# SLED.net
KiCad netlist of a schematic drawn in Altium Designer
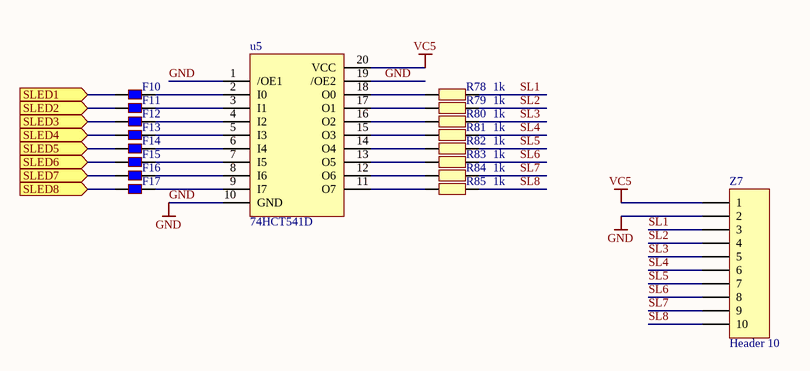
[diagram p0: SLED.SchDoc]

(export (version "E")
  (design (tool "Eeschema 10.0.6"))
  (components
    (comp (ref "F10")
      (value "BLM18BB141SN1D")
      (footprint "0805L")
      (description "Koralik ferrytowy")
      (libsource (lib "*") (part "1812"))
    )
    (comp (ref "F11")
      (value "BLM18BB141SN1D")
      (footprint "0805L")
      (description "Koralik ferrytowy")
      (libsource (lib "*") (part "1812"))
    )
    (comp (ref "F12")
      (value "BLM18BB141SN1D")
      (footprint "0805L")
      (description "Koralik ferrytowy")
      (libsource (lib "*") (part "1812"))
    )
    (comp (ref "F13")
      (value "BLM18BB141SN1D")
      (footprint "0805L")
      (description "Koralik ferrytowy")
      (libsource (lib "*") (part "1812"))
    )
    (comp (ref "F14")
      (value "BLM18BB141SN1D")
      (footprint "0805L")
      (description "Koralik ferrytowy")
      (libsource (lib "*") (part "1812"))
    )
    (comp (ref "F15")
      (value "BLM18BB141SN1D")
      (footprint "0805L")
      (description "Koralik ferrytowy")
      (libsource (lib "*") (part "1812"))
    )
    (comp (ref "F16")
      (value "BLM18BB141SN1D")
      (footprint "0805L")
      (description "Koralik ferrytowy")
      (libsource (lib "*") (part "1812"))
    )
    (comp (ref "F17")
      (value "BLM18BB141SN1D")
      (footprint "0805L")
      (description "Koralik ferrytowy")
      (libsource (lib "*") (part "1812"))
    )
    (comp (ref "R78") (value "1k") (footprint "0805R") (libsource (lib "*") (part "RES3")))
    (comp (ref "R79") (value "1k") (footprint "0805R") (libsource (lib "*") (part "RES3")))
    (comp (ref "R80") (value "1k") (footprint "0805R") (libsource (lib "*") (part "RES3")))
    (comp (ref "R81") (value "1k") (footprint "0805R") (libsource (lib "*") (part "RES3")))
    (comp (ref "R82") (value "1k") (footprint "0805R") (libsource (lib "*") (part "RES3")))
    (comp (ref "R83") (value "1k") (footprint "0805R") (libsource (lib "*") (part "RES3")))
    (comp (ref "R84") (value "1k") (footprint "0805R") (libsource (lib "*") (part "RES3")))
    (comp (ref "R85") (value "1k") (footprint "0805R") (libsource (lib "*") (part "RES3")))
    (comp (ref "u5") (value "74HCT541D") (footprint "SMD20") (libsource (lib "ElhosSchLib") (part "74541")))
    (comp (ref "Z7")
      (value "Header 10")
      (footprint "ARC-L-10-3.5")
      (description "Header, 10-Pin")
      (fields (field (name "PUBLISHER") "Altium Limited"))
      (libsource (lib "Miscellaneous Connectors") (part "Header 10"))
    )
  )
  (nets
    (net (code "1") (name "/SL1") (class "Default")
      (node (ref "R78") (pin "2") (pintype "passive"))
      (node (ref "Z7") (pin "3") (pinfunction "3_3") (pintype "passive"))
    )
    (net (code "2") (name "/SL2") (class "Default")
      (node (ref "R79") (pin "2") (pintype "passive"))
      (node (ref "Z7") (pin "4") (pinfunction "4_4") (pintype "passive"))
    )
    (net (code "3") (name "/SL3") (class "Default")
      (node (ref "R80") (pin "2") (pintype "passive"))
      (node (ref "Z7") (pin "5") (pinfunction "5_5") (pintype "passive"))
    )
    (net (code "4") (name "/SL4") (class "Default")
      (node (ref "R81") (pin "2") (pintype "passive"))
      (node (ref "Z7") (pin "6") (pinfunction "6_6") (pintype "passive"))
    )
    (net (code "5") (name "/SL5") (class "Default")
      (node (ref "R82") (pin "2") (pintype "passive"))
      (node (ref "Z7") (pin "7") (pinfunction "7_7") (pintype "passive"))
    )
    (net (code "6") (name "/SL6") (class "Default")
      (node (ref "R83") (pin "2") (pintype "passive"))
      (node (ref "Z7") (pin "8") (pinfunction "8_8") (pintype "passive"))
    )
    (net (code "7") (name "/SL7") (class "Default")
      (node (ref "R84") (pin "2") (pintype "passive"))
      (node (ref "Z7") (pin "9") (pinfunction "9_9") (pintype "passive"))
    )
    (net (code "8") (name "/SL8") (class "Default")
      (node (ref "R85") (pin "2") (pintype "passive"))
      (node (ref "Z7") (pin "10") (pinfunction "10_10") (pintype "passive"))
    )
    (net (code "9") (name "/SLED1") (class "Default") (node (ref "F10") (pin "2") (pintype "passive")))
    (net (code "10") (name "/SLED2") (class "Default") (node (ref "F11") (pin "2") (pintype "passive")))
    (net (code "11") (name "/SLED3") (class "Default") (node (ref "F12") (pin "2") (pintype "passive")))
    (net (code "12") (name "/SLED4") (class "Default") (node (ref "F13") (pin "2") (pintype "passive")))
    (net (code "13") (name "/SLED5") (class "Default") (node (ref "F14") (pin "2") (pintype "passive")))
    (net (code "14") (name "/SLED6") (class "Default") (node (ref "F15") (pin "2") (pintype "passive")))
    (net (code "15") (name "/SLED7") (class "Default") (node (ref "F16") (pin "2") (pintype "passive")))
    (net (code "16") (name "/SLED8") (class "Default") (node (ref "F17") (pin "2") (pintype "passive")))
    (net (code "17") (name "GND") (class "Default")
      (node (ref "Z7") (pin "2") (pinfunction "2_2") (pintype "passive"))
      (node (ref "u5") (pin "1") (pinfunction "/OE1_1") (pintype "passive"))
      (node (ref "u5") (pin "10") (pinfunction "GND_10") (pintype "passive"))
      (node (ref "u5") (pin "19") (pinfunction "/OE2_19") (pintype "passive"))
    )
    (net (code "18") (name "Net-(u5-I0)") (class "Default")
      (node (ref "F10") (pin "1") (pintype "passive"))
      (node (ref "u5") (pin "2") (pinfunction "I0_2") (pintype "passive"))
    )
    (net (code "19") (name "Net-(u5-I1)") (class "Default")
      (node (ref "F11") (pin "1") (pintype "passive"))
      (node (ref "u5") (pin "3") (pinfunction "I1_3") (pintype "passive"))
    )
    (net (code "20") (name "Net-(u5-I2)") (class "Default")
      (node (ref "F12") (pin "1") (pintype "passive"))
      (node (ref "u5") (pin "4") (pinfunction "I2_4") (pintype "passive"))
    )
    (net (code "21") (name "Net-(u5-I3)") (class "Default")
      (node (ref "F13") (pin "1") (pintype "passive"))
      (node (ref "u5") (pin "5") (pinfunction "I3_5") (pintype "passive"))
    )
    (net (code "22") (name "Net-(u5-I4)") (class "Default")
      (node (ref "F14") (pin "1") (pintype "passive"))
      (node (ref "u5") (pin "6") (pinfunction "I4_6") (pintype "passive"))
    )
    (net (code "23") (name "Net-(u5-I5)") (class "Default")
      (node (ref "F15") (pin "1") (pintype "passive"))
      (node (ref "u5") (pin "7") (pinfunction "I5_7") (pintype "passive"))
    )
    (net (code "24") (name "Net-(u5-I6)") (class "Default")
      (node (ref "F16") (pin "1") (pintype "passive"))
      (node (ref "u5") (pin "8") (pinfunction "I6_8") (pintype "passive"))
    )
    (net (code "25") (name "Net-(u5-I7)") (class "Default")
      (node (ref "F17") (pin "1") (pintype "passive"))
      (node (ref "u5") (pin "9") (pinfunction "I7_9") (pintype "passive"))
    )
    (net (code "26") (name "Net-(u5-O0)") (class "Default")
      (node (ref "R78") (pin "1") (pintype "passive"))
      (node (ref "u5") (pin "18") (pinfunction "O0_18") (pintype "passive"))
    )
    (net (code "27") (name "Net-(u5-O1)") (class "Default")
      (node (ref "R79") (pin "1") (pintype "passive"))
      (node (ref "u5") (pin "17") (pinfunction "O1_17") (pintype "passive"))
    )
    (net (code "28") (name "Net-(u5-O2)") (class "Default")
      (node (ref "R80") (pin "1") (pintype "passive"))
      (node (ref "u5") (pin "16") (pinfunction "O2_16") (pintype "passive"))
    )
    (net (code "29") (name "Net-(u5-O3)") (class "Default")
      (node (ref "R81") (pin "1") (pintype "passive"))
      (node (ref "u5") (pin "15") (pinfunction "O3_15") (pintype "passive"))
    )
    (net (code "30") (name "Net-(u5-O4)") (class "Default")
      (node (ref "R82") (pin "1") (pintype "passive"))
      (node (ref "u5") (pin "14") (pinfunction "O4_14") (pintype "passive"))
    )
    (net (code "31") (name "Net-(u5-O5)") (class "Default")
      (node (ref "R83") (pin "1") (pintype "passive"))
      (node (ref "u5") (pin "13") (pinfunction "O5_13") (pintype "passive"))
    )
    (net (code "32") (name "Net-(u5-O6)") (class "Default")
      (node (ref "R84") (pin "1") (pintype "passive"))
      (node (ref "u5") (pin "12") (pinfunction "O6_12") (pintype "passive"))
    )
    (net (code "33") (name "Net-(u5-O7)") (class "Default")
      (node (ref "R85") (pin "1") (pintype "passive"))
      (node (ref "u5") (pin "11") (pinfunction "O7_11") (pintype "passive"))
    )
    (net (code "34") (name "VC5") (class "Default")
      (node (ref "Z7") (pin "1") (pinfunction "1_1") (pintype "passive"))
      (node (ref "u5") (pin "20") (pinfunction "VCC_20") (pintype "passive"))
    )
  )
)
